# MCU_NODE.net
KiCad netlist of a schematic drawn in Altium Designer
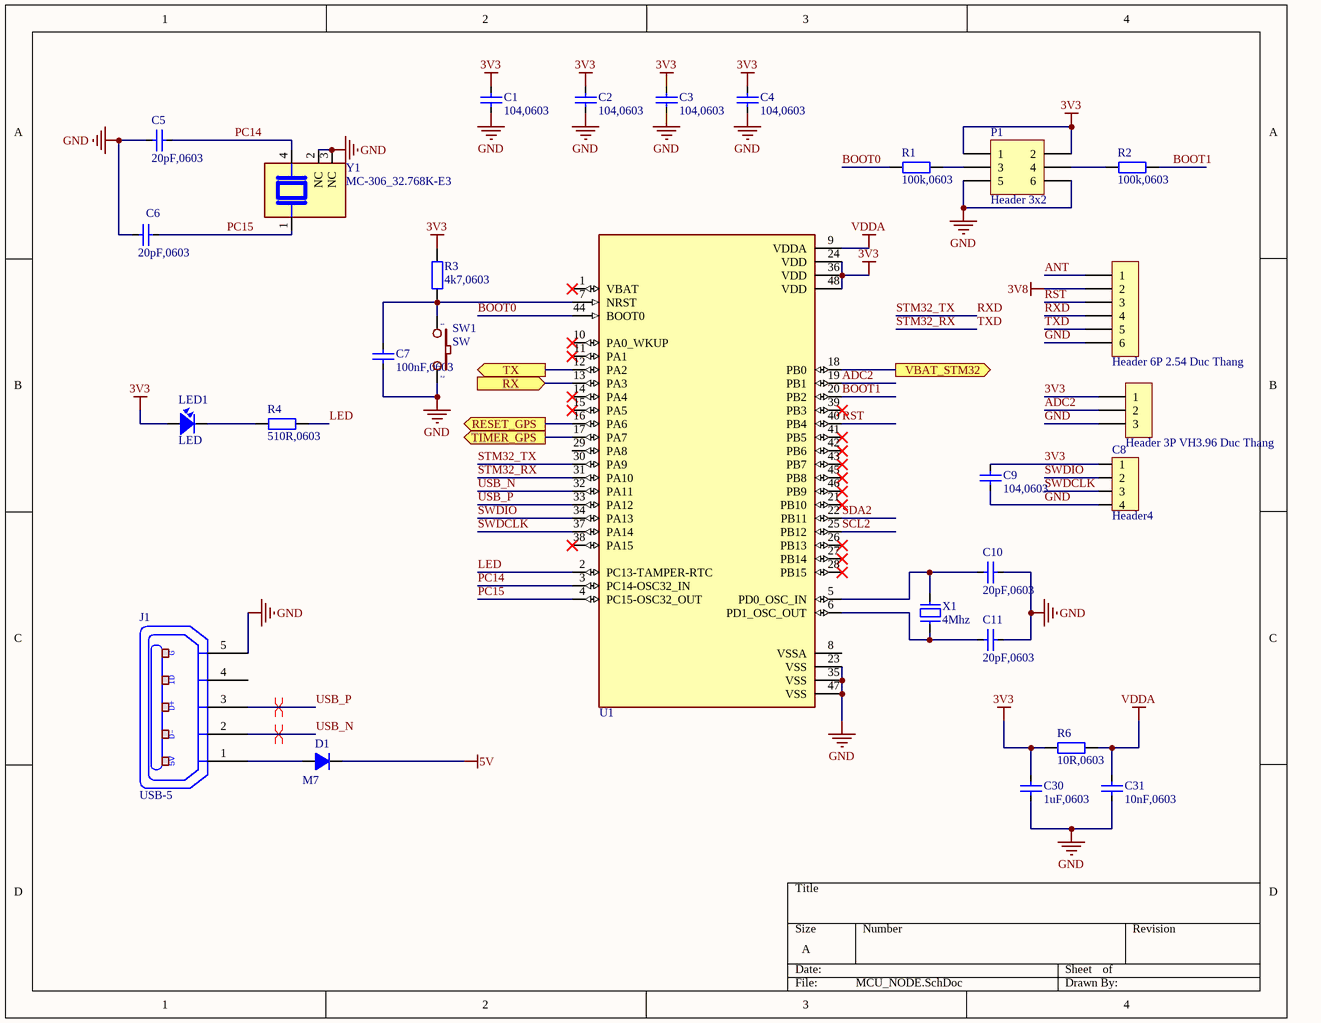
[diagram p0: MCU_NODE.SchDoc]

(export (version "E")
  (design (tool "Eeschema 10.0.6"))
  (components
    (comp (ref "C1")
      (value "104,0603")
      (footprint "CAP_0603")
      (description "Capacitor")
      (fields (field (name "PUBLISHER") "Altium Limited"))
      (libsource (lib "My Library") (part "CapSMD"))
    )
    (comp (ref "C2")
      (value "104,0603")
      (footprint "CAP_0603")
      (description "Capacitor")
      (fields (field (name "PUBLISHER") "Altium Limited"))
      (libsource (lib "My Library") (part "CapSMD"))
    )
    (comp (ref "C3")
      (value "104,0603")
      (footprint "CAP_0603")
      (description "Capacitor")
      (fields (field (name "PUBLISHER") "Altium Limited"))
      (libsource (lib "My Library") (part "CapSMD"))
    )
    (comp (ref "C4")
      (value "104,0603")
      (footprint "CAP_0603")
      (description "Capacitor")
      (fields (field (name "PUBLISHER") "Altium Limited"))
      (libsource (lib "My Library") (part "CapSMD"))
    )
    (comp (ref "C5")
      (value "20pF,0603")
      (footprint "CAP_0603")
      (description "Capacitor")
      (fields (field (name "PUBLISHER") "Altium Limited"))
      (libsource (lib "My Library") (part "CapSMD"))
    )
    (comp (ref "C6")
      (value "20pF,0603")
      (footprint "CAP_0603")
      (description "Capacitor")
      (fields (field (name "PUBLISHER") "Altium Limited"))
      (libsource (lib "My Library") (part "CapSMD"))
    )
    (comp (ref "C7")
      (value "100nF,0603")
      (footprint "CAP_0603")
      (description "Capacitor")
      (fields (field (name "PUBLISHER") "Altium Limited"))
      (libsource (lib "My Library") (part "CapSMD"))
    )
    (comp (ref "C8")
      (value "Header4")
      (footprint "JP4-D1C")
      (description "Header IDC, 4 x 1 Pin Vertical 2.54mm Pitch (Non-Boxed, Male)")
      (fields
        (field (name "MANUFACTURER") "Würth Elektronik eiSos GmbH")
        (field (name "PARTNO") "613002143121")
        (field (name "CREATED BY") "Karrer Zheng")
      )
      (libsource (lib "My Library") (part "Header4"))
    )
    (comp (ref "C9")
      (value "104,0603")
      (footprint "CAP_0603")
      (description "Capacitor")
      (fields (field (name "PUBLISHER") "Altium Limited"))
      (libsource (lib "My Library") (part "CapSMD"))
    )
    (comp (ref "C10")
      (value "20pF,0603")
      (footprint "CAP_0603")
      (description "Capacitor")
      (fields (field (name "PUBLISHER") "Altium Limited"))
      (libsource (lib "My Library") (part "CapSMD"))
    )
    (comp (ref "C11")
      (value "20pF,0603")
      (footprint "CAP_0603")
      (description "Capacitor")
      (fields (field (name "PUBLISHER") "Altium Limited"))
      (libsource (lib "My Library") (part "CapSMD"))
    )
    (comp (ref "C30")
      (value "1uF,0603")
      (footprint "CAP_0603")
      (description "Capacitor")
      (fields (field (name "PUBLISHER") "Altium Limited"))
      (libsource (lib "My Library") (part "CapSMD"))
    )
    (comp (ref "C31")
      (value "10nF,0603")
      (footprint "CAP_0603")
      (description "Capacitor")
      (fields (field (name "PUBLISHER") "Altium Limited"))
      (libsource (lib "My Library") (part "CapSMD"))
    )
    (comp (ref "D1")
      (value "M7")
      (footprint "SMA")
      (description "Diode 1A")
      (libsource (lib "Main") (part "D1A"))
    )
    (comp (ref "H1")
      (value "Header 6P 2.54 Duc Thang")
      (footprint "XH2.54M-6")
      (description "Cắm")
      (libsource (lib "Header") (part "Header 6P 2.54 Duc Thang"))
    )
    (comp (ref "H2")
      (value "Header 3P VH3.96 Duc Thang")
      (footprint "VH3.96M-3")
      (description "Cắm")
      (libsource (lib "Header") (part "Header 3P VH3.96 Duc Thang"))
    )
    (comp (ref "J1")
      (value "USB-5")
      (footprint "USB-M1")
      (fields
        (field (name "MANUFACTURER") "FCI")
        (field (name "MANUFACTURER PART NUMBER") "10118193-0001LF")
        (field (name ".CREATOR") "MM")
        (field (name ".CHECKED PCB") "RF")
        (field (name ".CHECKED SCH") "MM")
      )
      (libsource (lib "My Library") (part "USB-5"))
    )
    (comp (ref "LED1")
      (value "LED")
      (footprint "LED-0805-Blue")
      (description "LED Single colour Green and Red")
      (libsource (lib "My Library") (part "LED"))
    )
    (comp (ref "P1")
      (value "Header 3x2")
      (footprint "Header 3x2")
      (description "Header, 6-Pin, 2-Row")
      (fields (field (name "PUBLISHER") "Altium Limited"))
      (libsource (lib "hphonglib") (part "Header 3x2"))
    )
    (comp (ref "R1")
      (value "100k,0603")
      (footprint "RES-SMD-0603")
      (description "Resistor SMD")
      (fields
        (field (name "MANUFACTURER") "Generic Components")
        (field (name "PUBLISHER") "Altium Hobart Technology Centre")
      )
      (libsource (lib "My Library") (part "Resistor - SMD"))
    )
    (comp (ref "R2")
      (value "100k,0603")
      (footprint "RES-SMD-0603")
      (description "Resistor SMD")
      (fields
        (field (name "MANUFACTURER") "Generic Components")
        (field (name "PUBLISHER") "Altium Hobart Technology Centre")
      )
      (libsource (lib "My Library") (part "Resistor - SMD"))
    )
    (comp (ref "R3")
      (value "4k7,0603")
      (footprint "RES-SMD-0603")
      (description "Resistor SMD")
      (fields
        (field (name "MANUFACTURER") "Generic Components")
        (field (name "PUBLISHER") "Altium Hobart Technology Centre")
      )
      (libsource (lib "My Library") (part "Resistor - SMD"))
    )
    (comp (ref "R4")
      (value "510R,0603")
      (footprint "RES-SMD-0603")
      (description "Resistor SMD")
      (fields
        (field (name "MANUFACTURER") "Generic Components")
        (field (name "PUBLISHER") "Altium Hobart Technology Centre")
      )
      (libsource (lib "My Library") (part "Resistor - SMD"))
    )
    (comp (ref "R6")
      (value "10R,0603")
      (footprint "RES-SMD-0603")
      (description "Resistor SMD")
      (fields
        (field (name "MANUFACTURER") "Generic Components")
        (field (name "PUBLISHER") "Altium Hobart Technology Centre")
      )
      (libsource (lib "My Library") (part "Resistor - SMD"))
    )
    (comp (ref "SW1")
      (value "SW")
      (footprint "SW-SMD")
      (description "Switch button 2 pin")
      (libsource (lib "My Library") (part "SW2"))
    )
    (comp (ref "U1")
      (value "STM32")
      (footprint "LQFP 48")
      (description "STM32 ARM-based 32-bit MCU with 64 Kbytes Flash, 64-pin LQFP, Industrial Temperature")
      (libsource (lib "My Library") (part "STM32F103C8T6"))
    )
    (comp (ref "X1")
      (value "4Mhz")
      (footprint "XT2")
      (description "Crystal For all Crystal 2pin.")
      (libsource (lib "My Library") (part "XT2"))
    )
    (comp (ref "Y1")
      (value "MC-306_32.768K-E3")
      (footprint "XTAL_MC-306_32.768K-E3")
      (description "CRYSTAL 32.7680KHZ 6PF SMD")
      (fields (field (name "MF") "EPSON") (field (name "MP") "MC-306 32.768K-E3"))
      (libsource (lib "MC-306_32.768K-E3") (part "MC-306_32.768K-E3"))
    )
  )
  (nets
    (net (code "1") (name "/ADC2") (class "Default")
      (node (ref "H2") (pin "2") (pinfunction "2_2") (pintype "passive"))
      (node (ref "U1") (pin "19") (pinfunction "PB1_19") (pintype "bidirectional"))
    )
    (net (code "2") (name "/ANT") (class "Default")
      (node (ref "H1") (pin "1") (pinfunction "1_1") (pintype "passive"))
    )
    (net (code "3") (name "/BOOT0") (class "Default")
      (node (ref "R1") (pin "1") (pinfunction "1_1") (pintype "passive"))
      (node (ref "U1") (pin "44") (pinfunction "BOOT0_44") (pintype "input"))
    )
    (net (code "4") (name "/BOOT1") (class "Default")
      (node (ref "R2") (pin "2") (pinfunction "2_2") (pintype "passive"))
      (node (ref "U1") (pin "20") (pinfunction "PB2_20") (pintype "bidirectional"))
    )
    (net (code "5") (name "/LED") (class "Default")
      (node (ref "R4") (pin "2") (pinfunction "2_2") (pintype "passive"))
      (node (ref "U1") (pin "2") (pinfunction "PC13-TAMPER-RTC_2") (pintype "bidirectional"))
    )
    (net (code "6") (name "/PC14") (class "Default")
      (node (ref "C5") (pin "2") (pinfunction "2_2") (pintype "passive"))
      (node (ref "U1") (pin "3") (pinfunction "PC14-OSC32_IN_3") (pintype "bidirectional"))
      (node (ref "Y1") (pin "4") (pinfunction "2_4") (pintype "passive"))
    )
    (net (code "7") (name "/PC15") (class "Default")
      (node (ref "C6") (pin "2") (pinfunction "2_2") (pintype "passive"))
      (node (ref "U1") (pin "4") (pinfunction "PC15-OSC32_OUT_4") (pintype "bidirectional"))
      (node (ref "Y1") (pin "1") (pinfunction "1_1") (pintype "passive"))
    )
    (net (code "8") (name "/RESET_GPS") (class "Default")
      (node (ref "U1") (pin "16") (pinfunction "PA6_16") (pintype "bidirectional"))
    )
    (net (code "9") (name "/RST") (class "Default")
      (node (ref "H1") (pin "3") (pinfunction "3_3") (pintype "passive"))
      (node (ref "U1") (pin "40") (pinfunction "PB4_40") (pintype "bidirectional"))
    )
    (net (code "10") (name "/RX") (class "Default")
      (node (ref "U1") (pin "13") (pinfunction "PA3_13") (pintype "bidirectional"))
    )
    (net (code "11") (name "/RXD") (class "Default")
      (node (ref "H1") (pin "4") (pinfunction "4_4") (pintype "passive"))
      (node (ref "U1") (pin "30") (pinfunction "PA9_30") (pintype "bidirectional"))
    )
    (net (code "12") (name "/SCL2") (class "Default")
      (node (ref "U1") (pin "25") (pinfunction "PB12_25") (pintype "bidirectional"))
    )
    (net (code "13") (name "/SDA2") (class "Default")
      (node (ref "U1") (pin "22") (pinfunction "PB11_22") (pintype "bidirectional"))
    )
    (net (code "14") (name "/STM32_RX") (class "Default")
      (node (ref "H1") (pin "5") (pinfunction "5_5") (pintype "passive"))
      (node (ref "U1") (pin "31") (pinfunction "PA10_31") (pintype "bidirectional"))
    )
    (net (code "15") (name "/SWDCLK") (class "Default")
      (node (ref "C8") (pin "3") (pinfunction "3_3") (pintype "passive"))
      (node (ref "U1") (pin "37") (pinfunction "PA14_37") (pintype "bidirectional"))
    )
    (net (code "16") (name "/SWDIO") (class "Default")
      (node (ref "C8") (pin "2") (pinfunction "2_2") (pintype "passive"))
      (node (ref "U1") (pin "34") (pinfunction "PA13_34") (pintype "bidirectional"))
    )
    (net (code "17") (name "/TIMER_GPS") (class "Default")
      (node (ref "U1") (pin "17") (pinfunction "PA7_17") (pintype "bidirectional"))
    )
    (net (code "18") (name "/TX") (class "Default")
      (node (ref "U1") (pin "12") (pinfunction "PA2_12") (pintype "bidirectional"))
    )
    (net (code "19") (name "/USB_N") (class "Default")
      (node (ref "J1") (pin "2") (pinfunction "P2_2") (pintype "passive"))
      (node (ref "U1") (pin "32") (pinfunction "PA11_32") (pintype "bidirectional"))
    )
    (net (code "20") (name "/USB_P") (class "Default")
      (node (ref "J1") (pin "3") (pinfunction "P3_3") (pintype "passive"))
      (node (ref "U1") (pin "33") (pinfunction "PA12_33") (pintype "bidirectional"))
    )
    (net (code "21") (name "/VBAT_STM32") (class "Default")
      (node (ref "U1") (pin "18") (pinfunction "PB0_18") (pintype "bidirectional"))
    )
    (net (code "22") (name "3V3") (class "Default")
      (node (ref "C1") (pin "2") (pinfunction "2_2") (pintype "passive"))
      (node (ref "C2") (pin "2") (pinfunction "2_2") (pintype "passive"))
      (node (ref "C3") (pin "2") (pinfunction "2_2") (pintype "passive"))
      (node (ref "C30") (pin "2") (pinfunction "2_2") (pintype "passive"))
      (node (ref "C4") (pin "2") (pinfunction "2_2") (pintype "passive"))
      (node (ref "C8") (pin "1") (pinfunction "1_1") (pintype "passive"))
      (node (ref "C9") (pin "2") (pinfunction "2_2") (pintype "passive"))
      (node (ref "H2") (pin "1") (pinfunction "1_1") (pintype "passive"))
      (node (ref "LED1") (pin "1") (pinfunction "1_1") (pintype "passive"))
      (node (ref "P1") (pin "1") (pinfunction "1_1") (pintype "passive"))
      (node (ref "P1") (pin "2") (pinfunction "2_2") (pintype "passive"))
      (node (ref "R3") (pin "1") (pinfunction "1_1") (pintype "passive"))
      (node (ref "R6") (pin "1") (pinfunction "1_1") (pintype "passive"))
      (node (ref "U1") (pin "24") (pinfunction "VDD_24") (pintype "power_in"))
      (node (ref "U1") (pin "36") (pinfunction "VDD_36") (pintype "power_in"))
      (node (ref "U1") (pin "48") (pinfunction "VDD_48") (pintype "power_in"))
    )
    (net (code "23") (name "3V8") (class "Default")
      (node (ref "H1") (pin "2") (pinfunction "2_2") (pintype "passive"))
    )
    (net (code "24") (name "5V") (class "Default")
      (node (ref "D1") (pin "2") (pinfunction "K_2") (pintype "passive"))
    )
    (net (code "25") (name "GND") (class "Default")
      (node (ref "C1") (pin "1") (pinfunction "1_1") (pintype "passive"))
      (node (ref "C10") (pin "2") (pinfunction "2_2") (pintype "passive"))
      (node (ref "C11") (pin "2") (pinfunction "2_2") (pintype "passive"))
      (node (ref "C2") (pin "1") (pinfunction "1_1") (pintype "passive"))
      (node (ref "C3") (pin "1") (pinfunction "1_1") (pintype "passive"))
      (node (ref "C30") (pin "1") (pinfunction "1_1") (pintype "passive"))
      (node (ref "C31") (pin "1") (pinfunction "1_1") (pintype "passive"))
      (node (ref "C4") (pin "1") (pinfunction "1_1") (pintype "passive"))
      (node (ref "C5") (pin "1") (pinfunction "1_1") (pintype "passive"))
      (node (ref "C6") (pin "1") (pinfunction "1_1") (pintype "passive"))
      (node (ref "C7") (pin "1") (pinfunction "1_1") (pintype "passive"))
      (node (ref "C8") (pin "4") (pinfunction "4_4") (pintype "passive"))
      (node (ref "C9") (pin "1") (pinfunction "1_1") (pintype "passive"))
      (node (ref "H1") (pin "6") (pinfunction "6_6") (pintype "passive"))
      (node (ref "H2") (pin "3") (pinfunction "3_3") (pintype "passive"))
      (node (ref "J1") (pin "5") (pinfunction "P5_5") (pintype "passive"))
      (node (ref "P1") (pin "5") (pinfunction "5_5") (pintype "passive"))
      (node (ref "P1") (pin "6") (pinfunction "6_6") (pintype "passive"))
      (node (ref "SW1") (pin "2") (pinfunction "2_2") (pintype "passive"))
      (node (ref "U1") (pin "23") (pinfunction "VSS_23") (pintype "power_in"))
      (node (ref "U1") (pin "35") (pinfunction "VSS_35") (pintype "power_in"))
      (node (ref "U1") (pin "47") (pinfunction "VSS_47") (pintype "power_in"))
      (node (ref "Y1") (pin "2") (pinfunction "NC_2") (pintype "passive"))
      (node (ref "Y1") (pin "3") (pinfunction "NC_3") (pintype "passive"))
    )
    (net (code "26") (name "Net-(D1-A)") (class "Default")
      (node (ref "D1") (pin "1") (pinfunction "A_1") (pintype "passive"))
      (node (ref "J1") (pin "1") (pinfunction "P1_1") (pintype "passive"))
    )
    (net (code "27") (name "Net-(LED1-Pad2)") (class "Default")
      (node (ref "LED1") (pin "2") (pinfunction "2_2") (pintype "passive"))
      (node (ref "R4") (pin "1") (pinfunction "1_1") (pintype "passive"))
    )
    (net (code "28") (name "Net-(P1-Pad3)") (class "Default")
      (node (ref "P1") (pin "3") (pinfunction "3_3") (pintype "passive"))
      (node (ref "R1") (pin "2") (pinfunction "2_2") (pintype "passive"))
    )
    (net (code "29") (name "Net-(P1-Pad4)") (class "Default")
      (node (ref "P1") (pin "4") (pinfunction "4_4") (pintype "passive"))
      (node (ref "R2") (pin "1") (pinfunction "1_1") (pintype "passive"))
    )
    (net (code "30") (name "Net-(U1-NRST)") (class "Default")
      (node (ref "C7") (pin "2") (pinfunction "2_2") (pintype "passive"))
      (node (ref "R3") (pin "2") (pinfunction "2_2") (pintype "passive"))
      (node (ref "SW1") (pin "1") (pinfunction "1_1") (pintype "passive"))
      (node (ref "U1") (pin "7") (pinfunction "NRST_7") (pintype "input"))
    )
    (net (code "31") (name "Net-(U1-PD0_OSC_IN)") (class "Default")
      (node (ref "C10") (pin "1") (pinfunction "1_1") (pintype "passive"))
      (node (ref "U1") (pin "5") (pinfunction "PD0_OSC_IN_5") (pintype "bidirectional"))
      (node (ref "X1") (pin "2") (pinfunction "2_2") (pintype "passive"))
    )
    (net (code "32") (name "Net-(U1-PD1_OSC_OUT)") (class "Default")
      (node (ref "C11") (pin "1") (pinfunction "1_1") (pintype "passive"))
      (node (ref "U1") (pin "6") (pinfunction "PD1_OSC_OUT_6") (pintype "bidirectional"))
      (node (ref "X1") (pin "1") (pinfunction "1_1") (pintype "passive"))
    )
    (net (code "33") (name "VDDA") (class "Default")
      (node (ref "C31") (pin "2") (pinfunction "2_2") (pintype "passive"))
      (node (ref "R6") (pin "2") (pinfunction "2_2") (pintype "passive"))
      (node (ref "U1") (pin "9") (pinfunction "VDDA_9") (pintype "power_in"))
    )
    (net (code "34") (name "unconnected-(J1-P4-Pad4)") (class "Default")
      (node (ref "J1") (pin "4") (pinfunction "P4_4") (pintype "passive"))
    )
    (net (code "35") (name "unconnected-(U1-PA0_WKUP-Pad10)") (class "Default")
      (node (ref "U1") (pin "10") (pinfunction "PA0_WKUP_10") (pintype "bidirectional+no_connect"))
    )
    (net (code "36") (name "unconnected-(U1-PA1-Pad11)") (class "Default")
      (node (ref "U1") (pin "11") (pinfunction "PA1_11") (pintype "bidirectional+no_connect"))
    )
    (net (code "37") (name "unconnected-(U1-PA4-Pad14)") (class "Default")
      (node (ref "U1") (pin "14") (pinfunction "PA4_14") (pintype "bidirectional+no_connect"))
    )
    (net (code "38") (name "unconnected-(U1-PA5-Pad15)") (class "Default")
      (node (ref "U1") (pin "15") (pinfunction "PA5_15") (pintype "bidirectional+no_connect"))
    )
    (net (code "39") (name "unconnected-(U1-PA8-Pad29)") (class "Default")
      (node (ref "U1") (pin "29") (pinfunction "PA8_29") (pintype "bidirectional"))
    )
    (net (code "40") (name "unconnected-(U1-PA15-Pad38)") (class "Default")
      (node (ref "U1") (pin "38") (pinfunction "PA15_38") (pintype "bidirectional+no_connect"))
    )
    (net (code "41") (name "unconnected-(U1-PB3-Pad39)") (class "Default")
      (node (ref "U1") (pin "39") (pinfunction "PB3_39") (pintype "bidirectional+no_connect"))
    )
    (net (code "42") (name "unconnected-(U1-PB5-Pad41)") (class "Default")
      (node (ref "U1") (pin "41") (pinfunction "PB5_41") (pintype "bidirectional+no_connect"))
    )
    (net (code "43") (name "unconnected-(U1-PB6-Pad42)") (class "Default")
      (node (ref "U1") (pin "42") (pinfunction "PB6_42") (pintype "bidirectional+no_connect"))
    )
    (net (code "44") (name "unconnected-(U1-PB7-Pad43)") (class "Default")
      (node (ref "U1") (pin "43") (pinfunction "PB7_43") (pintype "bidirectional+no_connect"))
    )
    (net (code "45") (name "unconnected-(U1-PB8-Pad45)") (class "Default")
      (node (ref "U1") (pin "45") (pinfunction "PB8_45") (pintype "bidirectional+no_connect"))
    )
    (net (code "46") (name "unconnected-(U1-PB9-Pad46)") (class "Default")
      (node (ref "U1") (pin "46") (pinfunction "PB9_46") (pintype "bidirectional+no_connect"))
    )
    (net (code "47") (name "unconnected-(U1-PB10-Pad21)") (class "Default")
      (node (ref "U1") (pin "21") (pinfunction "PB10_21") (pintype "bidirectional+no_connect"))
    )
    (net (code "48") (name "unconnected-(U1-PB13-Pad26)") (class "Default")
      (node (ref "U1") (pin "26") (pinfunction "PB13_26") (pintype "bidirectional+no_connect"))
    )
    (net (code "49") (name "unconnected-(U1-PB14-Pad27)") (class "Default")
      (node (ref "U1") (pin "27") (pinfunction "PB14_27") (pintype "bidirectional+no_connect"))
    )
    (net (code "50") (name "unconnected-(U1-PB15-Pad28)") (class "Default")
      (node (ref "U1") (pin "28") (pinfunction "PB15_28") (pintype "bidirectional+no_connect"))
    )
    (net (code "51") (name "unconnected-(U1-VBAT-Pad1)") (class "Default")
      (node (ref "U1") (pin "1") (pinfunction "VBAT_1") (pintype "bidirectional+no_connect"))
    )
    (net (code "52") (name "unconnected-(U1-VSSA-Pad8)") (class "Default")
      (node (ref "U1") (pin "8") (pinfunction "VSSA_8") (pintype "power_in"))
    )
  )
)
